# fpga_pwr.net
KiCad netlist of a schematic drawn in Altium Designer
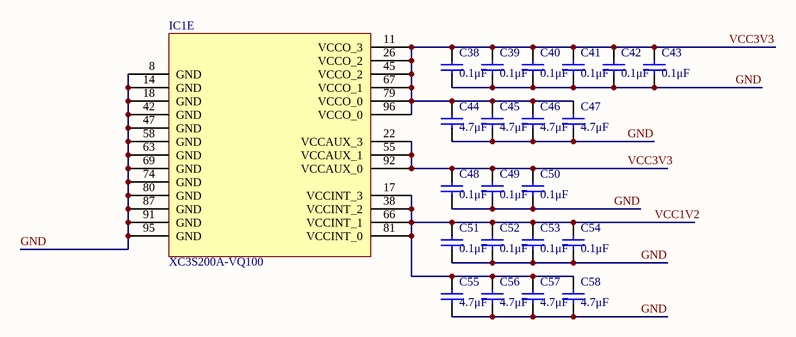
[diagram p0: fpga_pwr.SchDoc]

(export (version "E")
  (design (tool "Eeschema 10.0.6"))
  (components
    (comp (ref "C38")
      (value "0.1μF")
      (footprint "1608[0603]")
      (description "Capacitor (Semiconductor SIM Model)")
      (fields (field (name "Comment") "Cap Semi") (field (name "PUBLISHER") "Altium Limited"))
      (libsource (lib "Miscellaneous Devices") (part "Cap Semi"))
    )
    (comp (ref "C39")
      (value "0.1μF")
      (footprint "1608[0603]")
      (description "Capacitor (Semiconductor SIM Model)")
      (fields (field (name "Comment") "Cap Semi") (field (name "PUBLISHER") "Altium Limited"))
      (libsource (lib "Miscellaneous Devices") (part "Cap Semi"))
    )
    (comp (ref "C40")
      (value "0.1μF")
      (footprint "1608[0603]")
      (description "Capacitor (Semiconductor SIM Model)")
      (fields (field (name "Comment") "Cap Semi") (field (name "PUBLISHER") "Altium Limited"))
      (libsource (lib "Miscellaneous Devices") (part "Cap Semi"))
    )
    (comp (ref "C41")
      (value "0.1μF")
      (footprint "1608[0603]")
      (description "Capacitor (Semiconductor SIM Model)")
      (fields (field (name "Comment") "Cap Semi") (field (name "PUBLISHER") "Altium Limited"))
      (libsource (lib "Miscellaneous Devices") (part "Cap Semi"))
    )
    (comp (ref "C42")
      (value "0.1μF")
      (footprint "1608[0603]")
      (description "Capacitor (Semiconductor SIM Model)")
      (fields (field (name "Comment") "Cap Semi") (field (name "PUBLISHER") "Altium Limited"))
      (libsource (lib "Miscellaneous Devices") (part "Cap Semi"))
    )
    (comp (ref "C43")
      (value "0.1μF")
      (footprint "1608[0603]")
      (description "Capacitor (Semiconductor SIM Model)")
      (fields (field (name "Comment") "Cap Semi") (field (name "PUBLISHER") "Altium Limited"))
      (libsource (lib "Miscellaneous Devices") (part "Cap Semi"))
    )
    (comp (ref "C44")
      (value "4.7μF")
      (footprint "1608[0603]")
      (description "Capacitor (Semiconductor SIM Model)")
      (fields (field (name "Comment") "Cap Semi") (field (name "PUBLISHER") "Altium Limited"))
      (libsource (lib "Miscellaneous Devices") (part "Cap Semi"))
    )
    (comp (ref "C45")
      (value "4.7μF")
      (footprint "1608[0603]")
      (description "Capacitor (Semiconductor SIM Model)")
      (fields (field (name "Comment") "Cap Semi") (field (name "PUBLISHER") "Altium Limited"))
      (libsource (lib "Miscellaneous Devices") (part "Cap Semi"))
    )
    (comp (ref "C46")
      (value "4.7μF")
      (footprint "1608[0603]")
      (description "Capacitor (Semiconductor SIM Model)")
      (fields (field (name "Comment") "Cap Semi") (field (name "PUBLISHER") "Altium Limited"))
      (libsource (lib "Miscellaneous Devices") (part "Cap Semi"))
    )
    (comp (ref "C47")
      (value "4.7μF")
      (footprint "1608[0603]")
      (description "Capacitor (Semiconductor SIM Model)")
      (fields (field (name "Comment") "Cap Semi") (field (name "PUBLISHER") "Altium Limited"))
      (libsource (lib "Miscellaneous Devices") (part "Cap Semi"))
    )
    (comp (ref "C48")
      (value "0.1μF")
      (footprint "1608[0603]")
      (description "Capacitor (Semiconductor SIM Model)")
      (fields (field (name "Comment") "Cap Semi") (field (name "PUBLISHER") "Altium Limited"))
      (libsource (lib "Miscellaneous Devices") (part "Cap Semi"))
    )
    (comp (ref "C49")
      (value "0.1μF")
      (footprint "1608[0603]")
      (description "Capacitor (Semiconductor SIM Model)")
      (fields (field (name "Comment") "Cap Semi") (field (name "PUBLISHER") "Altium Limited"))
      (libsource (lib "Miscellaneous Devices") (part "Cap Semi"))
    )
    (comp (ref "C50")
      (value "0.1μF")
      (footprint "1608[0603]")
      (description "Capacitor (Semiconductor SIM Model)")
      (fields (field (name "Comment") "Cap Semi") (field (name "PUBLISHER") "Altium Limited"))
      (libsource (lib "Miscellaneous Devices") (part "Cap Semi"))
    )
    (comp (ref "C51")
      (value "0.1μF")
      (footprint "1608[0603]")
      (description "Capacitor (Semiconductor SIM Model)")
      (fields (field (name "Comment") "Cap Semi") (field (name "PUBLISHER") "Altium Limited"))
      (libsource (lib "Miscellaneous Devices") (part "Cap Semi"))
    )
    (comp (ref "C52")
      (value "0.1μF")
      (footprint "1608[0603]")
      (description "Capacitor (Semiconductor SIM Model)")
      (fields (field (name "Comment") "Cap Semi") (field (name "PUBLISHER") "Altium Limited"))
      (libsource (lib "Miscellaneous Devices") (part "Cap Semi"))
    )
    (comp (ref "C53")
      (value "0.1μF")
      (footprint "1608[0603]")
      (description "Capacitor (Semiconductor SIM Model)")
      (fields (field (name "Comment") "Cap Semi") (field (name "PUBLISHER") "Altium Limited"))
      (libsource (lib "Miscellaneous Devices") (part "Cap Semi"))
    )
    (comp (ref "C54")
      (value "0.1μF")
      (footprint "1608[0603]")
      (description "Capacitor (Semiconductor SIM Model)")
      (fields (field (name "Comment") "Cap Semi") (field (name "PUBLISHER") "Altium Limited"))
      (libsource (lib "Miscellaneous Devices") (part "Cap Semi"))
    )
    (comp (ref "C55")
      (value "4.7μF")
      (footprint "1608[0603]")
      (description "Capacitor (Semiconductor SIM Model)")
      (fields (field (name "Comment") "Cap Semi") (field (name "PUBLISHER") "Altium Limited"))
      (libsource (lib "Miscellaneous Devices") (part "Cap Semi"))
    )
    (comp (ref "C56")
      (value "4.7μF")
      (footprint "1608[0603]")
      (description "Capacitor (Semiconductor SIM Model)")
      (fields (field (name "Comment") "Cap Semi") (field (name "PUBLISHER") "Altium Limited"))
      (libsource (lib "Miscellaneous Devices") (part "Cap Semi"))
    )
    (comp (ref "C57")
      (value "4.7μF")
      (footprint "1608[0603]")
      (description "Capacitor (Semiconductor SIM Model)")
      (fields (field (name "Comment") "Cap Semi") (field (name "PUBLISHER") "Altium Limited"))
      (libsource (lib "Miscellaneous Devices") (part "Cap Semi"))
    )
    (comp (ref "C58")
      (value "4.7μF")
      (footprint "1608[0603]")
      (description "Capacitor (Semiconductor SIM Model)")
      (fields (field (name "Comment") "Cap Semi") (field (name "PUBLISHER") "Altium Limited"))
      (libsource (lib "Miscellaneous Devices") (part "Cap Semi"))
    )
    (comp (ref "IC1")
      (value "XC3S200A-VQ100")
      (footprint "QFP50P1600X1600X120-100N")
      (libsource (lib "nir_usb") (part "XC3S200A-VQ100"))
    )
  )
  (nets
    (net (code "1") (name "/GND") (class "Default")
      (node (ref "C38") (pin "1") (pinfunction "1_1") (pintype "passive"))
      (node (ref "C39") (pin "1") (pinfunction "1_1") (pintype "passive"))
      (node (ref "C40") (pin "1") (pinfunction "1_1") (pintype "passive"))
      (node (ref "C41") (pin "1") (pinfunction "1_1") (pintype "passive"))
      (node (ref "C42") (pin "1") (pinfunction "1_1") (pintype "passive"))
      (node (ref "C43") (pin "1") (pinfunction "1_1") (pintype "passive"))
      (node (ref "C44") (pin "1") (pinfunction "1_1") (pintype "passive"))
      (node (ref "C45") (pin "1") (pinfunction "1_1") (pintype "passive"))
      (node (ref "C46") (pin "1") (pinfunction "1_1") (pintype "passive"))
      (node (ref "C47") (pin "1") (pinfunction "1_1") (pintype "passive"))
      (node (ref "C48") (pin "1") (pinfunction "1_1") (pintype "passive"))
      (node (ref "C49") (pin "1") (pinfunction "1_1") (pintype "passive"))
      (node (ref "C50") (pin "1") (pinfunction "1_1") (pintype "passive"))
      (node (ref "C51") (pin "1") (pinfunction "1_1") (pintype "passive"))
      (node (ref "C52") (pin "1") (pinfunction "1_1") (pintype "passive"))
      (node (ref "C53") (pin "1") (pinfunction "1_1") (pintype "passive"))
      (node (ref "C54") (pin "1") (pinfunction "1_1") (pintype "passive"))
      (node (ref "C55") (pin "1") (pinfunction "1_1") (pintype "passive"))
      (node (ref "C56") (pin "1") (pinfunction "1_1") (pintype "passive"))
      (node (ref "C57") (pin "1") (pinfunction "1_1") (pintype "passive"))
      (node (ref "C58") (pin "1") (pinfunction "1_1") (pintype "passive"))
      (node (ref "IC1") (pin "14") (pinfunction "GND_14") (pintype "passive"))
      (node (ref "IC1") (pin "18") (pinfunction "GND_18") (pintype "passive"))
      (node (ref "IC1") (pin "42") (pinfunction "GND_42") (pintype "passive"))
      (node (ref "IC1") (pin "47") (pinfunction "GND_47") (pintype "passive"))
      (node (ref "IC1") (pin "58") (pinfunction "GND_58") (pintype "passive"))
      (node (ref "IC1") (pin "63") (pinfunction "GND_63") (pintype "passive"))
      (node (ref "IC1") (pin "69") (pinfunction "GND_69") (pintype "passive"))
      (node (ref "IC1") (pin "74") (pinfunction "GND_74") (pintype "passive"))
      (node (ref "IC1") (pin "8") (pinfunction "GND_8") (pintype "passive"))
      (node (ref "IC1") (pin "80") (pinfunction "GND_80") (pintype "passive"))
      (node (ref "IC1") (pin "87") (pinfunction "GND_87") (pintype "passive"))
      (node (ref "IC1") (pin "91") (pinfunction "GND_91") (pintype "passive"))
      (node (ref "IC1") (pin "95") (pinfunction "GND_95") (pintype "passive"))
    )
    (net (code "2") (name "/VCC1V2") (class "Default")
      (node (ref "C51") (pin "2") (pinfunction "2_2") (pintype "passive"))
      (node (ref "C52") (pin "2") (pinfunction "2_2") (pintype "passive"))
      (node (ref "C53") (pin "2") (pinfunction "2_2") (pintype "passive"))
      (node (ref "C54") (pin "2") (pinfunction "2_2") (pintype "passive"))
      (node (ref "C55") (pin "2") (pinfunction "2_2") (pintype "passive"))
      (node (ref "C56") (pin "2") (pinfunction "2_2") (pintype "passive"))
      (node (ref "C57") (pin "2") (pinfunction "2_2") (pintype "passive"))
      (node (ref "C58") (pin "2") (pinfunction "2_2") (pintype "passive"))
      (node (ref "IC1") (pin "17") (pinfunction "VCCINT_3_17") (pintype "passive"))
      (node (ref "IC1") (pin "38") (pinfunction "VCCINT_2_38") (pintype "passive"))
      (node (ref "IC1") (pin "66") (pinfunction "VCCINT_1_66") (pintype "passive"))
      (node (ref "IC1") (pin "81") (pinfunction "VCCINT_0_81") (pintype "passive"))
    )
    (net (code "3") (name "/VCC3V3") (class "Default")
      (node (ref "C38") (pin "2") (pinfunction "2_2") (pintype "passive"))
      (node (ref "C39") (pin "2") (pinfunction "2_2") (pintype "passive"))
      (node (ref "C40") (pin "2") (pinfunction "2_2") (pintype "passive"))
      (node (ref "C41") (pin "2") (pinfunction "2_2") (pintype "passive"))
      (node (ref "C42") (pin "2") (pinfunction "2_2") (pintype "passive"))
      (node (ref "C43") (pin "2") (pinfunction "2_2") (pintype "passive"))
      (node (ref "C44") (pin "2") (pinfunction "2_2") (pintype "passive"))
      (node (ref "C45") (pin "2") (pinfunction "2_2") (pintype "passive"))
      (node (ref "C46") (pin "2") (pinfunction "2_2") (pintype "passive"))
      (node (ref "C47") (pin "2") (pinfunction "2_2") (pintype "passive"))
      (node (ref "C48") (pin "2") (pinfunction "2_2") (pintype "passive"))
      (node (ref "C49") (pin "2") (pinfunction "2_2") (pintype "passive"))
      (node (ref "C50") (pin "2") (pinfunction "2_2") (pintype "passive"))
      (node (ref "IC1") (pin "11") (pinfunction "VCCO_3_11") (pintype "passive"))
      (node (ref "IC1") (pin "22") (pinfunction "VCCAUX_3_22") (pintype "passive"))
      (node (ref "IC1") (pin "26") (pinfunction "VCCO_2_26") (pintype "passive"))
      (node (ref "IC1") (pin "45") (pinfunction "VCCO_2_45") (pintype "passive"))
      (node (ref "IC1") (pin "55") (pinfunction "VCCAUX_1_55") (pintype "passive"))
      (node (ref "IC1") (pin "67") (pinfunction "VCCO_1_67") (pintype "passive"))
      (node (ref "IC1") (pin "79") (pinfunction "VCCO_0_79") (pintype "passive"))
      (node (ref "IC1") (pin "92") (pinfunction "VCCAUX_0_92") (pintype "passive"))
      (node (ref "IC1") (pin "96") (pinfunction "VCCO_0_96") (pintype "passive"))
    )
  )
)
